# PassProgrammer.net
KiCad netlist of a schematic drawn in Altium Designer
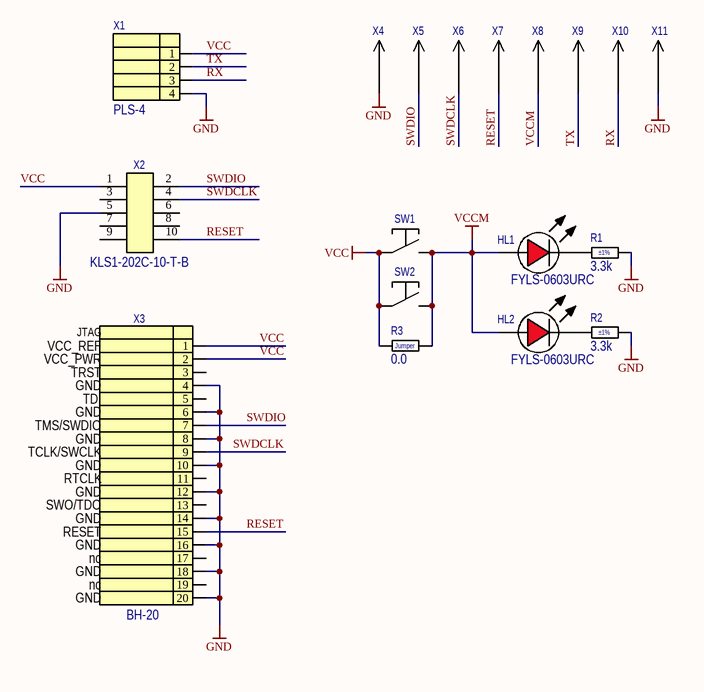
[diagram p0: PassProgrammer.SchDoc]

(export (version "E")
  (design (tool "Eeschema 10.0.6"))
  (components
    (comp (ref "HL1")
      (value "FYLS-0603URC")
      (footprint "LED_0603_RED")
      (description "Led 0603 Red")
      (fields (field (name "MANUFACTURER") "FORYARD"))
      (libsource (lib "altium") (part "LED_RED"))
    )
    (comp (ref "HL2")
      (value "FYLS-0603URC")
      (footprint "LED_0603_RED")
      (description "Led 0603 Red")
      (fields (field (name "MANUFACTURER") "FORYARD"))
      (libsource (lib "altium") (part "LED_RED"))
    )
    (comp (ref "R1")
      (value "3.3k")
      (footprint "R0603 (1608 Metric) N")
      (description "RES SMD 3.3K OHM 1% 1/10W 0603")
      (fields
        (field (name "TOLERANCE") "±1%")
        (field (name "PART NUMBER") "RC0603FR-073K3L")
        (field (name "MANUFACTURER") "Yageo")
      )
      (libsource (lib "rlc") (part "RES"))
    )
    (comp (ref "R2")
      (value "3.3k")
      (footprint "R0603 (1608 Metric) N")
      (description "RES SMD 3.3K OHM 1% 1/10W 0603")
      (fields
        (field (name "TOLERANCE") "±1%")
        (field (name "PART NUMBER") "RC0603FR-073K3L")
        (field (name "MANUFACTURER") "Yageo")
      )
      (libsource (lib "rlc") (part "RES"))
    )
    (comp (ref "R3")
      (value "0.0")
      (footprint "R0603 (1608 Metric) N")
      (description "RES SMD 0.0OHM JUMPER 1/10W 0603")
      (fields
        (field (name "TOLERANCE") "Jumper")
        (field (name "PART NUMBER") "RC0603JR-070RL")
        (field (name "MANUFACTURER") "Yageo")
      )
      (libsource (lib "rlc") (part "RES"))
    )
    (comp (ref "SW1")
      (value "EVQ-PBC04M")
      (footprint "TACT SWITCH 6MM SMD")
      (description "SWITCH TACTILE SPST-NO 0.02A 15V")
      (fields (field (name "MANUFACTURER") "Panasonic Electronic Components"))
      (libsource (lib "switch") (part "Button NO"))
    )
    (comp (ref "SW2")
      (value "EVQ-PBC04M")
      (footprint "TACT SWITCH 6MM SMD")
      (description "SWITCH TACTILE SPST-NO 0.02A 15V")
      (fields (field (name "MANUFACTURER") "Panasonic Electronic Components"))
      (libsource (lib "switch") (part "Button NO"))
    )
    (comp (ref "X1")
      (value "PLS-4")
      (footprint "PLS-4")
      (libsource (lib "terminals") (part "Terminal_4_pin"))
    )
    (comp (ref "X2")
      (value "KLS1-202C-10-T-B")
      (footprint "KLS1-202C-10-T-B")
      (description "5*2 pin 	1.27x1.27mm Pitch Box Header Connector Height 4.9mm")
      (fields (field (name "MANUFACTURER") "KLS"))
      (libsource (lib "terminals") (part "Terminal_2x5_pin"))
    )
    (comp (ref "X3")
      (value "BH-20")
      (footprint "BH-20-H")
      (libsource (lib "terminals") (part "Terminal_2x10_JTAG"))
    )
    (comp (ref "X4")
      (value "POGOPIN-P75-B1")
      (footprint "POGO-PIN 1,02*15,85")
      (libsource (lib "terminals") (part "PogoPin"))
    )
    (comp (ref "X5")
      (value "POGOPIN-P75-B1")
      (footprint "POGO-PIN 1,02*15,85")
      (libsource (lib "terminals") (part "PogoPin"))
    )
    (comp (ref "X6")
      (value "POGOPIN-P75-B1")
      (footprint "POGO-PIN 1,02*15,85")
      (libsource (lib "terminals") (part "PogoPin"))
    )
    (comp (ref "X7")
      (value "POGOPIN-P75-B1")
      (footprint "POGO-PIN 1,02*15,85")
      (libsource (lib "terminals") (part "PogoPin"))
    )
    (comp (ref "X8")
      (value "POGOPIN-P75-B1")
      (footprint "POGO-PIN 1,02*15,85")
      (libsource (lib "terminals") (part "PogoPin"))
    )
    (comp (ref "X9")
      (value "POGOPIN-P75-B1")
      (footprint "POGO-PIN 1,02*15,85")
      (libsource (lib "terminals") (part "PogoPin"))
    )
    (comp (ref "X10")
      (value "POGOPIN-P75-B1")
      (footprint "POGO-PIN 1,02*15,85")
      (libsource (lib "terminals") (part "PogoPin"))
    )
    (comp (ref "X11")
      (value "POGOPIN-P75-B1")
      (footprint "POGO-PIN 1,02*15,85")
      (libsource (lib "terminals") (part "PogoPin"))
    )
  )
  (nets
    (net (code "1") (name "/RESET") (class "Default")
      (node (ref "X2") (pin "10") (pinfunction "10_10") (pintype "passive"))
      (node (ref "X3") (pin "15") (pinfunction "15_15") (pintype "passive"))
      (node (ref "X7") (pin "1") (pinfunction "1_1") (pintype "passive"))
    )
    (net (code "2") (name "/RX") (class "Default")
      (node (ref "X1") (pin "3") (pinfunction "3_3") (pintype "passive"))
      (node (ref "X10") (pin "1") (pinfunction "1_1") (pintype "passive"))
    )
    (net (code "3") (name "/SWDCLK") (class "Default")
      (node (ref "X2") (pin "4") (pinfunction "4_4") (pintype "passive"))
      (node (ref "X3") (pin "9") (pinfunction "9_9") (pintype "passive"))
      (node (ref "X6") (pin "1") (pinfunction "1_1") (pintype "passive"))
    )
    (net (code "4") (name "/SWDIO") (class "Default")
      (node (ref "X2") (pin "2") (pinfunction "2_2") (pintype "passive"))
      (node (ref "X3") (pin "7") (pinfunction "7_7") (pintype "passive"))
      (node (ref "X5") (pin "1") (pinfunction "1_1") (pintype "passive"))
    )
    (net (code "5") (name "/TX") (class "Default")
      (node (ref "X1") (pin "2") (pinfunction "2_2") (pintype "passive"))
      (node (ref "X9") (pin "1") (pinfunction "1_1") (pintype "passive"))
    )
    (net (code "6") (name "GND") (class "Default")
      (node (ref "R1") (pin "2") (pinfunction "2_2") (pintype "passive"))
      (node (ref "R2") (pin "2") (pinfunction "2_2") (pintype "passive"))
      (node (ref "X1") (pin "4") (pinfunction "4_4") (pintype "passive"))
      (node (ref "X11") (pin "1") (pinfunction "1_1") (pintype "passive"))
      (node (ref "X2") (pin "5") (pinfunction "5_5") (pintype "passive"))
      (node (ref "X3") (pin "10") (pinfunction "10_10") (pintype "passive"))
      (node (ref "X3") (pin "12") (pinfunction "12_12") (pintype "passive"))
      (node (ref "X3") (pin "14") (pinfunction "14_14") (pintype "passive"))
      (node (ref "X3") (pin "16") (pinfunction "16_16") (pintype "passive"))
      (node (ref "X3") (pin "18") (pinfunction "18_18") (pintype "passive"))
      (node (ref "X3") (pin "20") (pinfunction "20_20") (pintype "passive"))
      (node (ref "X3") (pin "4") (pinfunction "4_4") (pintype "passive"))
      (node (ref "X3") (pin "6") (pinfunction "6_6") (pintype "passive"))
      (node (ref "X3") (pin "8") (pinfunction "8_8") (pintype "passive"))
      (node (ref "X4") (pin "1") (pinfunction "1_1") (pintype "passive"))
    )
    (net (code "7") (name "Net-(HL1-PadC)") (class "Default")
      (node (ref "HL1") (pin "C") (pinfunction "C_C") (pintype "passive"))
      (node (ref "R1") (pin "1") (pinfunction "1_1") (pintype "passive"))
    )
    (net (code "8") (name "Net-(HL2-PadC)") (class "Default")
      (node (ref "HL2") (pin "C") (pinfunction "C_C") (pintype "passive"))
      (node (ref "R2") (pin "1") (pinfunction "1_1") (pintype "passive"))
    )
    (net (code "9") (name "VCC") (class "Default")
      (node (ref "R3") (pin "1") (pinfunction "1_1") (pintype "passive"))
      (node (ref "SW1") (pin "1") (pinfunction "1_1") (pintype "passive"))
      (node (ref "SW2") (pin "1") (pinfunction "1_1") (pintype "passive"))
      (node (ref "X1") (pin "1") (pinfunction "1_1") (pintype "passive"))
      (node (ref "X2") (pin "1") (pinfunction "1_1") (pintype "passive"))
      (node (ref "X3") (pin "1") (pinfunction "1_1") (pintype "passive"))
      (node (ref "X3") (pin "2") (pinfunction "2_2") (pintype "passive"))
    )
    (net (code "10") (name "VCCM") (class "Default")
      (node (ref "HL1") (pin "A") (pinfunction "A_A") (pintype "passive"))
      (node (ref "HL2") (pin "A") (pinfunction "A_A") (pintype "passive"))
      (node (ref "R3") (pin "2") (pinfunction "2_2") (pintype "passive"))
      (node (ref "SW1") (pin "2") (pinfunction "2_2") (pintype "passive"))
      (node (ref "SW2") (pin "2") (pinfunction "2_2") (pintype "passive"))
      (node (ref "X8") (pin "1") (pinfunction "1_1") (pintype "passive"))
    )
    (net (code "11") (name "unconnected-(X2-Pad3)") (class "Default")
      (node (ref "X2") (pin "3") (pinfunction "3_3") (pintype "passive"))
    )
    (net (code "12") (name "unconnected-(X2-Pad6)") (class "Default")
      (node (ref "X2") (pin "6") (pinfunction "6_6") (pintype "passive"))
    )
    (net (code "13") (name "unconnected-(X2-Pad7)") (class "Default")
      (node (ref "X2") (pin "7") (pinfunction "7_7") (pintype "passive"))
    )
    (net (code "14") (name "unconnected-(X2-Pad8)") (class "Default")
      (node (ref "X2") (pin "8") (pinfunction "8_8") (pintype "passive"))
    )
    (net (code "15") (name "unconnected-(X2-Pad9)") (class "Default")
      (node (ref "X2") (pin "9") (pinfunction "9_9") (pintype "passive"))
    )
    (net (code "16") (name "unconnected-(X3-Pad3)") (class "Default")
      (node (ref "X3") (pin "3") (pinfunction "3_3") (pintype "passive"))
    )
    (net (code "17") (name "unconnected-(X3-Pad5)") (class "Default")
      (node (ref "X3") (pin "5") (pinfunction "5_5") (pintype "passive"))
    )
    (net (code "18") (name "unconnected-(X3-Pad11)") (class "Default")
      (node (ref "X3") (pin "11") (pinfunction "11_11") (pintype "passive"))
    )
    (net (code "19") (name "unconnected-(X3-Pad13)") (class "Default")
      (node (ref "X3") (pin "13") (pinfunction "13_13") (pintype "passive"))
    )
    (net (code "20") (name "unconnected-(X3-Pad17)") (class "Default")
      (node (ref "X3") (pin "17") (pinfunction "17_17") (pintype "passive"))
    )
    (net (code "21") (name "unconnected-(X3-Pad19)") (class "Default")
      (node (ref "X3") (pin "19") (pinfunction "19_19") (pintype "passive"))
    )
  )
)
